# CapPiano.net
KiCad netlist of a schematic drawn in EasyEDA Pro
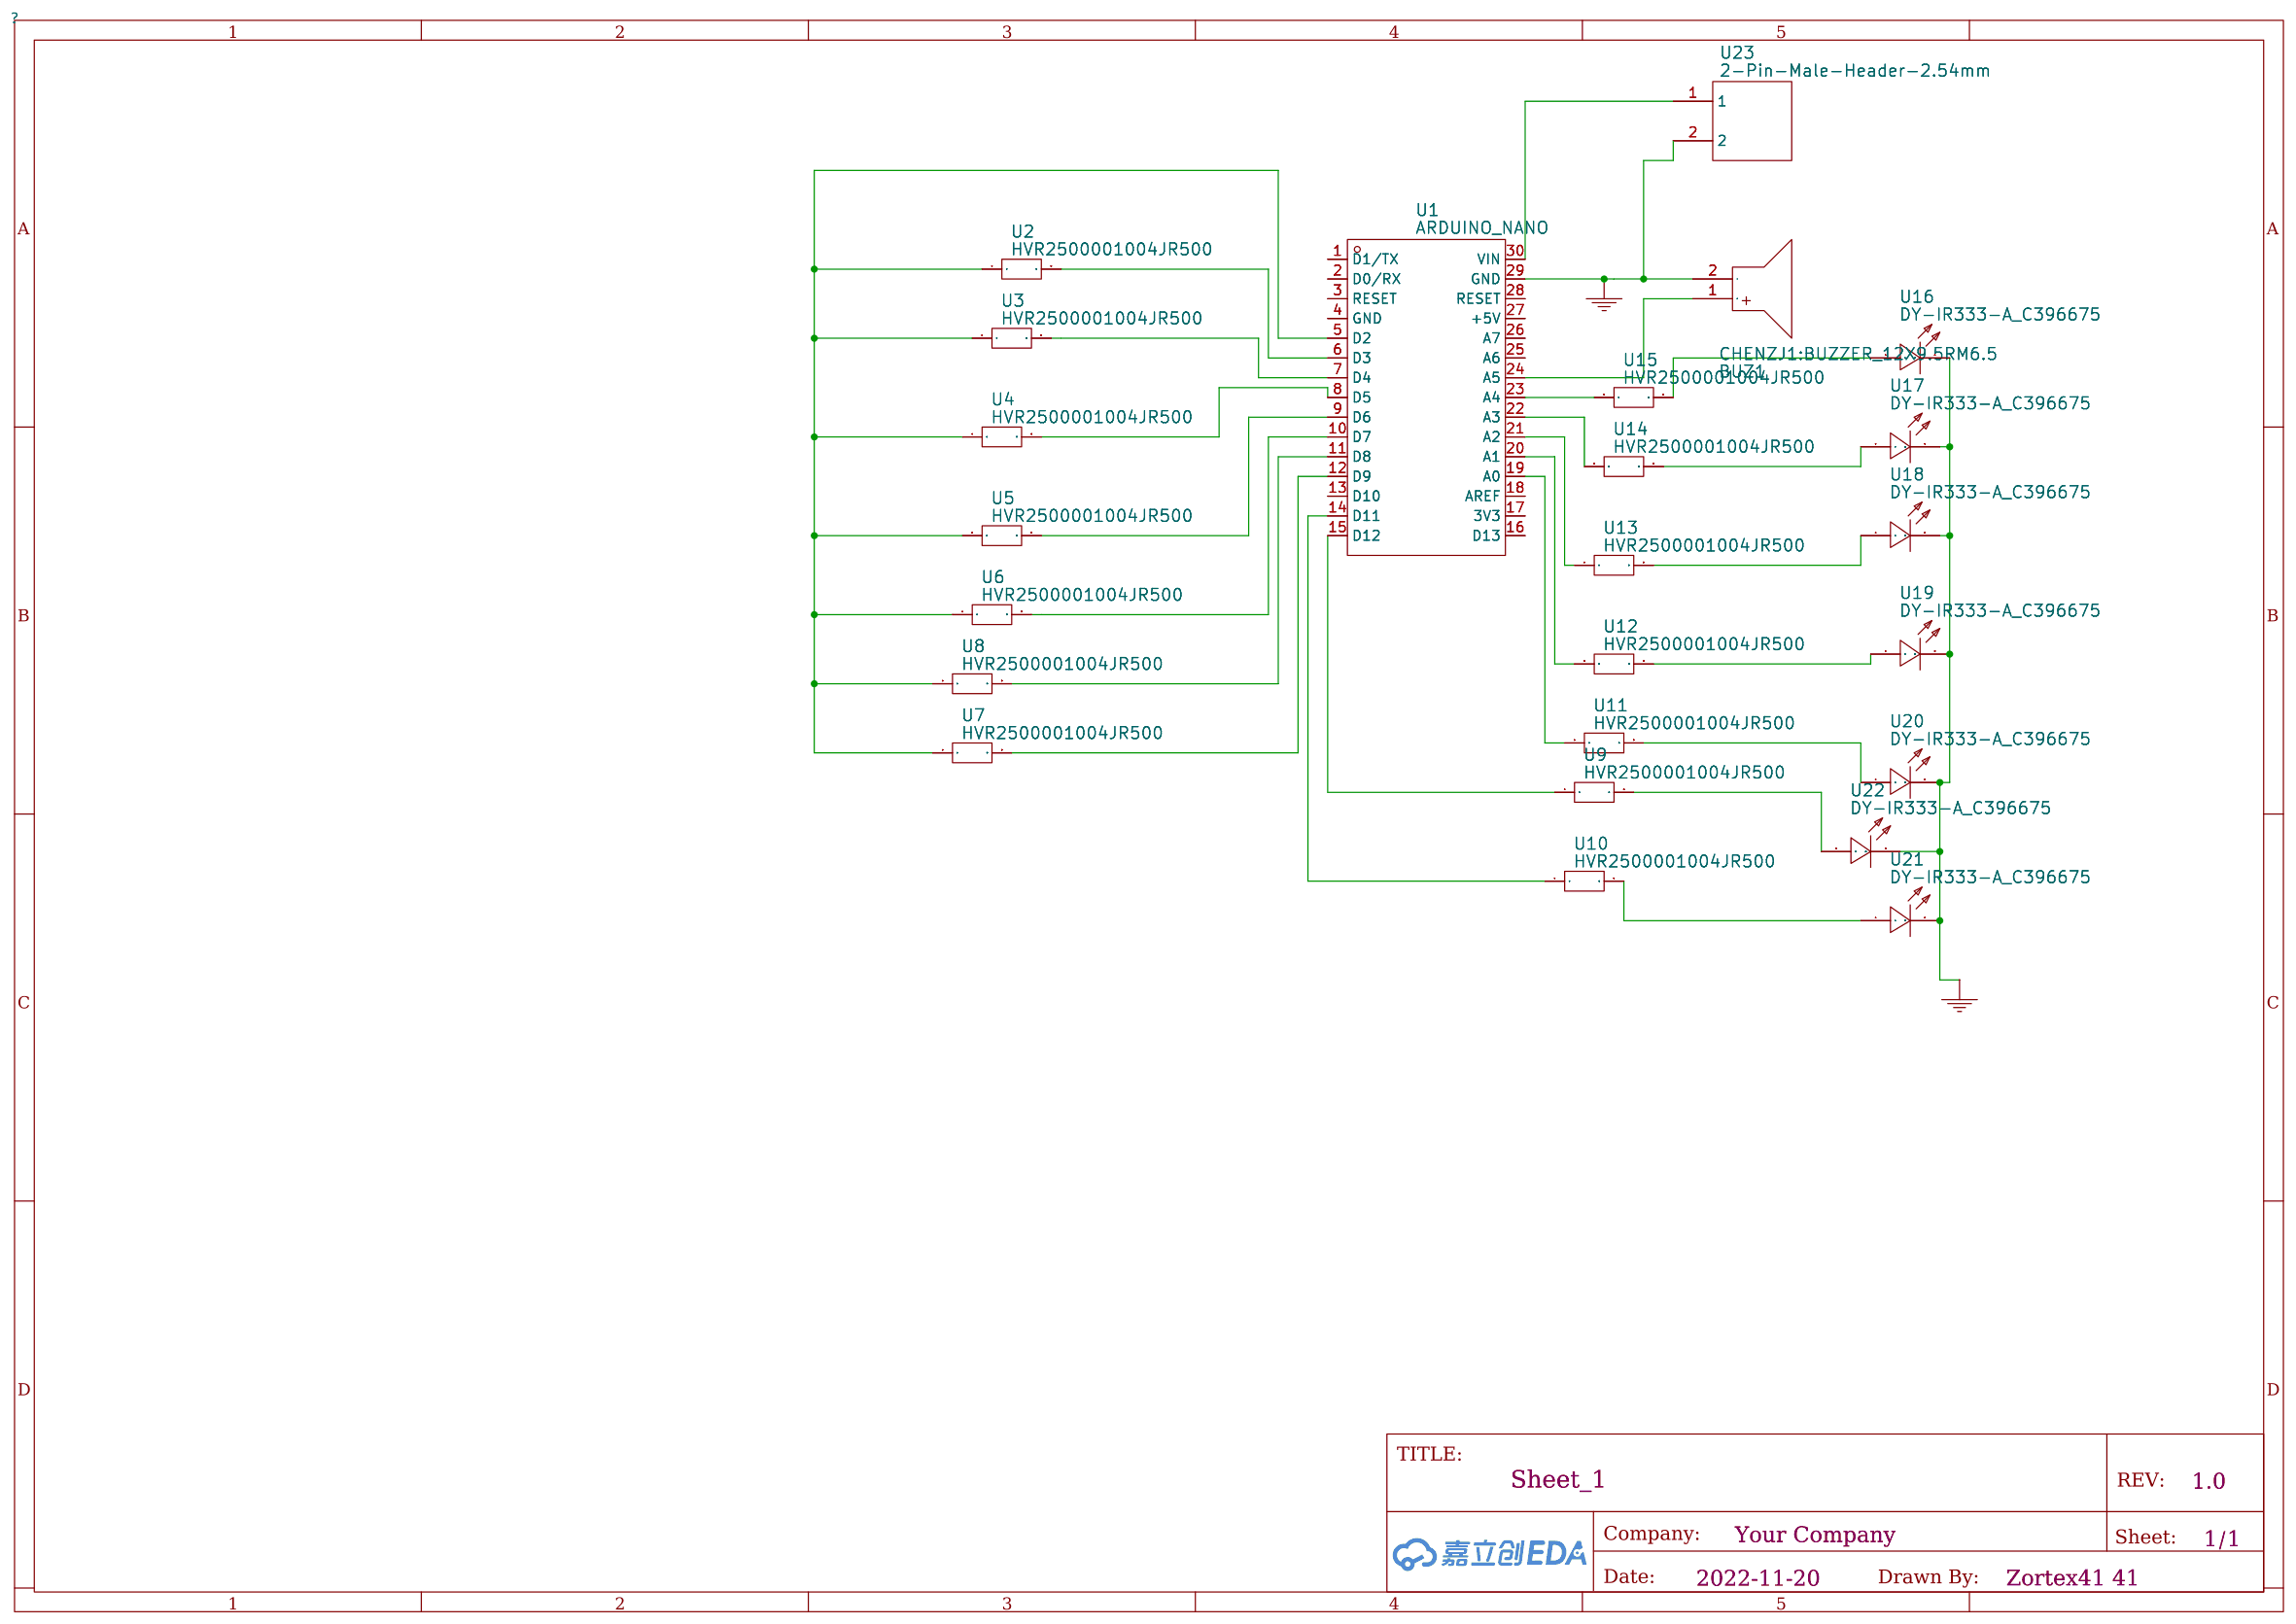
[diagram p0: schematic sheet]

(export (version "E")
  (design (tool "Eeschema 10.0.6"))
  (components
    (comp (ref "BUZ1")
      (value "CHENZJ1:BUZZER_12X9.5RM6.5")
      (footprint "easyedapro:BUZ-TH_BD12.0-P6.50-D0.6_SEA-1285F")
      (fields (field (name "Manufacturer Part") "chenzj1:Buzzer_12x9.5RM6.5"))
      (libsource (lib "easyedapro") (part "CHENZJ1{colon}BUZZER_12X9.5RM6.5"))
    )
    (comp (ref "U1")
      (value "ARDUINO_NANO")
      (footprint "easyedapro:COMM-TH_ARDUINO_NANO")
      (libsource (lib "easyedapro") (part "ARDUINO_NANO"))
    )
    (comp (ref "U2")
      (value "HVR2500001004JR500")
      (footprint "easyedapro:RES-TH_BD2.5-L7.0-P11.00-D0.6")
      (fields (field (name "Manufacturer") "VISHAY(威世)"))
      (libsource (lib "easyedapro") (part "HVR2500001004JR500"))
    )
    (comp (ref "U3")
      (value "HVR2500001004JR500")
      (footprint "easyedapro:RES-TH_BD2.5-L7.0-P11.00-D0.6")
      (fields (field (name "Manufacturer") "VISHAY(威世)"))
      (libsource (lib "easyedapro") (part "HVR2500001004JR500"))
    )
    (comp (ref "U4")
      (value "HVR2500001004JR500")
      (footprint "easyedapro:RES-TH_BD2.5-L7.0-P11.00-D0.6")
      (fields (field (name "Manufacturer") "VISHAY(威世)"))
      (libsource (lib "easyedapro") (part "HVR2500001004JR500"))
    )
    (comp (ref "U5")
      (value "HVR2500001004JR500")
      (footprint "easyedapro:RES-TH_BD2.5-L7.0-P11.00-D0.6")
      (fields (field (name "Manufacturer") "VISHAY(威世)"))
      (libsource (lib "easyedapro") (part "HVR2500001004JR500"))
    )
    (comp (ref "U6")
      (value "HVR2500001004JR500")
      (footprint "easyedapro:RES-TH_BD2.5-L7.0-P11.00-D0.6")
      (fields (field (name "Manufacturer") "VISHAY(威世)"))
      (libsource (lib "easyedapro") (part "HVR2500001004JR500"))
    )
    (comp (ref "U7")
      (value "HVR2500001004JR500")
      (footprint "easyedapro:RES-TH_BD2.5-L7.0-P11.00-D0.6")
      (fields (field (name "Manufacturer") "VISHAY(威世)"))
      (libsource (lib "easyedapro") (part "HVR2500001004JR500"))
    )
    (comp (ref "U8")
      (value "HVR2500001004JR500")
      (footprint "easyedapro:RES-TH_BD2.5-L7.0-P11.00-D0.6")
      (fields (field (name "Manufacturer") "VISHAY(威世)"))
      (libsource (lib "easyedapro") (part "HVR2500001004JR500"))
    )
    (comp (ref "U9")
      (value "HVR2500001004JR500")
      (footprint "easyedapro:RES-TH_BD2.5-L7.0-P11.00-D0.6")
      (fields (field (name "Manufacturer") "VISHAY(威世)"))
      (libsource (lib "easyedapro") (part "HVR2500001004JR500"))
    )
    (comp (ref "U10")
      (value "HVR2500001004JR500")
      (footprint "easyedapro:RES-TH_BD2.5-L7.0-P11.00-D0.6")
      (fields (field (name "Manufacturer") "VISHAY(威世)"))
      (libsource (lib "easyedapro") (part "HVR2500001004JR500"))
    )
    (comp (ref "U11")
      (value "HVR2500001004JR500")
      (footprint "easyedapro:RES-TH_BD2.5-L7.0-P11.00-D0.6")
      (fields (field (name "Manufacturer") "VISHAY(威世)"))
      (libsource (lib "easyedapro") (part "HVR2500001004JR500"))
    )
    (comp (ref "U12")
      (value "HVR2500001004JR500")
      (footprint "easyedapro:RES-TH_BD2.5-L7.0-P11.00-D0.6")
      (fields (field (name "Manufacturer") "VISHAY(威世)"))
      (libsource (lib "easyedapro") (part "HVR2500001004JR500"))
    )
    (comp (ref "U13")
      (value "HVR2500001004JR500")
      (footprint "easyedapro:RES-TH_BD2.5-L7.0-P11.00-D0.6")
      (fields (field (name "Manufacturer") "VISHAY(威世)"))
      (libsource (lib "easyedapro") (part "HVR2500001004JR500"))
    )
    (comp (ref "U14")
      (value "HVR2500001004JR500")
      (footprint "easyedapro:RES-TH_BD2.5-L7.0-P11.00-D0.6")
      (fields (field (name "Manufacturer") "VISHAY(威世)"))
      (libsource (lib "easyedapro") (part "HVR2500001004JR500"))
    )
    (comp (ref "U15")
      (value "HVR2500001004JR500")
      (footprint "easyedapro:RES-TH_BD2.5-L7.0-P11.00-D0.6")
      (fields (field (name "Manufacturer") "VISHAY(威世)"))
      (libsource (lib "easyedapro") (part "HVR2500001004JR500"))
    )
    (comp (ref "U16")
      (value "DY-IR333-A_C396675")
      (footprint "easyedapro:LED-TH_BD5.9-P2.54-FD")
      (fields (field (name "Manufacturer Part") "DY-IR333-A") (field (name "Manufacturer") "TONYU"))
      (libsource (lib "easyedapro") (part "DY-IR333-A_C396675"))
    )
    (comp (ref "U17")
      (value "DY-IR333-A_C396675")
      (footprint "easyedapro:LED-TH_BD5.9-P2.54-FD")
      (fields (field (name "Manufacturer Part") "DY-IR333-A") (field (name "Manufacturer") "TONYU"))
      (libsource (lib "easyedapro") (part "DY-IR333-A_C396675"))
    )
    (comp (ref "U18")
      (value "DY-IR333-A_C396675")
      (footprint "easyedapro:LED-TH_BD5.9-P2.54-FD")
      (fields (field (name "Manufacturer Part") "DY-IR333-A") (field (name "Manufacturer") "TONYU"))
      (libsource (lib "easyedapro") (part "DY-IR333-A_C396675"))
    )
    (comp (ref "U19")
      (value "DY-IR333-A_C396675")
      (footprint "easyedapro:LED-TH_BD5.9-P2.54-FD")
      (fields (field (name "Manufacturer Part") "DY-IR333-A") (field (name "Manufacturer") "TONYU"))
      (libsource (lib "easyedapro") (part "DY-IR333-A_C396675"))
    )
    (comp (ref "U20")
      (value "DY-IR333-A_C396675")
      (footprint "easyedapro:LED-TH_BD5.9-P2.54-FD")
      (fields (field (name "Manufacturer Part") "DY-IR333-A") (field (name "Manufacturer") "TONYU"))
      (libsource (lib "easyedapro") (part "DY-IR333-A_C396675"))
    )
    (comp (ref "U21")
      (value "DY-IR333-A_C396675")
      (footprint "easyedapro:LED-TH_BD5.9-P2.54-FD")
      (fields (field (name "Manufacturer Part") "DY-IR333-A") (field (name "Manufacturer") "TONYU"))
      (libsource (lib "easyedapro") (part "DY-IR333-A_C396675"))
    )
    (comp (ref "U22")
      (value "DY-IR333-A_C396675")
      (footprint "easyedapro:LED-TH_BD5.9-P2.54-FD")
      (fields (field (name "Manufacturer Part") "DY-IR333-A") (field (name "Manufacturer") "TONYU"))
      (libsource (lib "easyedapro") (part "DY-IR333-A_C396675"))
    )
    (comp (ref "U23")
      (value "2-Pin-Male-Header-2.54mm")
      (footprint "easyedapro:2-PIN-MALE-HEADER-2.54MM")
      (libsource (lib "easyedapro") (part "2-Pin-Male-Header-2.54mm"))
    )
  )
  (nets
    (net (code "1") (name "GND") (class "Default")
      (node (ref "BUZ1") (pin "2") (pinfunction "-_2") (pintype "input"))
      (node (ref "U1") (pin "29") (pinfunction "GND_29") (pintype "input"))
      (node (ref "U16") (pin "2") (pinfunction "C_2") (pintype "input"))
      (node (ref "U17") (pin "2") (pinfunction "C_2") (pintype "input"))
      (node (ref "U18") (pin "2") (pinfunction "C_2") (pintype "input"))
      (node (ref "U19") (pin "2") (pinfunction "C_2") (pintype "input"))
      (node (ref "U20") (pin "2") (pinfunction "C_2") (pintype "input"))
      (node (ref "U21") (pin "2") (pinfunction "C_2") (pintype "input"))
      (node (ref "U22") (pin "2") (pinfunction "C_2") (pintype "input"))
      (node (ref "U23") (pin "2") (pinfunction "2_2") (pintype "input"))
    )
    (net (code "2") (name "Net-(BUZ1-+)") (class "Default")
      (node (ref "BUZ1") (pin "1") (pinfunction "+_1") (pintype "input"))
      (node (ref "U1") (pin "24") (pinfunction "A5_24") (pintype "input"))
    )
    (net (code "3") (name "Net-(U1-A0)") (class "Default")
      (node (ref "U1") (pin "19") (pinfunction "A0_19") (pintype "input"))
      (node (ref "U11") (pin "1") (pinfunction "1_1") (pintype "input"))
    )
    (net (code "4") (name "Net-(U1-A1)") (class "Default")
      (node (ref "U1") (pin "20") (pinfunction "A1_20") (pintype "input"))
      (node (ref "U12") (pin "1") (pinfunction "1_1") (pintype "input"))
    )
    (net (code "5") (name "Net-(U1-A2)") (class "Default")
      (node (ref "U1") (pin "21") (pinfunction "A2_21") (pintype "input"))
      (node (ref "U13") (pin "1") (pinfunction "1_1") (pintype "input"))
    )
    (net (code "6") (name "Net-(U1-A3)") (class "Default")
      (node (ref "U1") (pin "22") (pinfunction "A3_22") (pintype "input"))
      (node (ref "U14") (pin "1") (pinfunction "1_1") (pintype "input"))
    )
    (net (code "7") (name "Net-(U1-A4)") (class "Default")
      (node (ref "U1") (pin "23") (pinfunction "A4_23") (pintype "input"))
      (node (ref "U15") (pin "1") (pinfunction "1_1") (pintype "input"))
    )
    (net (code "8") (name "Net-(U1-D2)") (class "Default")
      (node (ref "U1") (pin "5") (pinfunction "D2_5") (pintype "input"))
      (node (ref "U2") (pin "1") (pinfunction "1_1") (pintype "input"))
      (node (ref "U3") (pin "1") (pinfunction "1_1") (pintype "input"))
      (node (ref "U4") (pin "1") (pinfunction "1_1") (pintype "input"))
      (node (ref "U5") (pin "1") (pinfunction "1_1") (pintype "input"))
      (node (ref "U6") (pin "1") (pinfunction "1_1") (pintype "input"))
      (node (ref "U7") (pin "1") (pinfunction "1_1") (pintype "input"))
      (node (ref "U8") (pin "1") (pinfunction "1_1") (pintype "input"))
    )
    (net (code "9") (name "Net-(U1-D3)") (class "Default")
      (node (ref "U1") (pin "6") (pinfunction "D3_6") (pintype "input"))
      (node (ref "U2") (pin "2") (pinfunction "2_2") (pintype "input"))
    )
    (net (code "10") (name "Net-(U1-D4)") (class "Default")
      (node (ref "U1") (pin "7") (pinfunction "D4_7") (pintype "input"))
      (node (ref "U3") (pin "2") (pinfunction "2_2") (pintype "input"))
    )
    (net (code "11") (name "Net-(U1-D5)") (class "Default")
      (node (ref "U1") (pin "8") (pinfunction "D5_8") (pintype "input"))
      (node (ref "U4") (pin "2") (pinfunction "2_2") (pintype "input"))
    )
    (net (code "12") (name "Net-(U1-D6)") (class "Default")
      (node (ref "U1") (pin "9") (pinfunction "D6_9") (pintype "input"))
      (node (ref "U5") (pin "2") (pinfunction "2_2") (pintype "input"))
    )
    (net (code "13") (name "Net-(U1-D7)") (class "Default")
      (node (ref "U1") (pin "10") (pinfunction "D7_10") (pintype "input"))
      (node (ref "U6") (pin "2") (pinfunction "2_2") (pintype "input"))
    )
    (net (code "14") (name "Net-(U1-D8)") (class "Default")
      (node (ref "U1") (pin "11") (pinfunction "D8_11") (pintype "input"))
      (node (ref "U8") (pin "2") (pinfunction "2_2") (pintype "input"))
    )
    (net (code "15") (name "Net-(U1-D9)") (class "Default")
      (node (ref "U1") (pin "12") (pinfunction "D9_12") (pintype "input"))
      (node (ref "U7") (pin "2") (pinfunction "2_2") (pintype "input"))
    )
    (net (code "16") (name "Net-(U1-D11)") (class "Default")
      (node (ref "U1") (pin "14") (pinfunction "D11_14") (pintype "input"))
      (node (ref "U10") (pin "1") (pinfunction "1_1") (pintype "input"))
    )
    (net (code "17") (name "Net-(U1-D12)") (class "Default")
      (node (ref "U1") (pin "15") (pinfunction "D12_15") (pintype "input"))
      (node (ref "U9") (pin "1") (pinfunction "1_1") (pintype "input"))
    )
    (net (code "18") (name "Net-(U1-VIN)") (class "Default")
      (node (ref "U1") (pin "30") (pinfunction "VIN_30") (pintype "input"))
      (node (ref "U23") (pin "1") (pinfunction "1_1") (pintype "input"))
    )
    (net (code "19") (name "Net-(U16-A)") (class "Default")
      (node (ref "U15") (pin "2") (pinfunction "2_2") (pintype "input"))
      (node (ref "U16") (pin "1") (pinfunction "A_1") (pintype "input"))
    )
    (net (code "20") (name "Net-(U17-A)") (class "Default")
      (node (ref "U14") (pin "2") (pinfunction "2_2") (pintype "input"))
      (node (ref "U17") (pin "1") (pinfunction "A_1") (pintype "input"))
    )
    (net (code "21") (name "Net-(U18-A)") (class "Default")
      (node (ref "U13") (pin "2") (pinfunction "2_2") (pintype "input"))
      (node (ref "U18") (pin "1") (pinfunction "A_1") (pintype "input"))
    )
    (net (code "22") (name "Net-(U19-A)") (class "Default")
      (node (ref "U12") (pin "2") (pinfunction "2_2") (pintype "input"))
      (node (ref "U19") (pin "1") (pinfunction "A_1") (pintype "input"))
    )
    (net (code "23") (name "Net-(U20-A)") (class "Default")
      (node (ref "U11") (pin "2") (pinfunction "2_2") (pintype "input"))
      (node (ref "U20") (pin "1") (pinfunction "A_1") (pintype "input"))
    )
    (net (code "24") (name "Net-(U21-A)") (class "Default")
      (node (ref "U10") (pin "2") (pinfunction "2_2") (pintype "input"))
      (node (ref "U21") (pin "1") (pinfunction "A_1") (pintype "input"))
    )
    (net (code "25") (name "Net-(U22-A)") (class "Default")
      (node (ref "U22") (pin "1") (pinfunction "A_1") (pintype "input"))
      (node (ref "U9") (pin "2") (pinfunction "2_2") (pintype "input"))
    )
    (net (code "26") (name "unconnected-(U1-+5V-Pad27)") (class "Default")
      (node (ref "U1") (pin "27") (pinfunction "+5V_27") (pintype "input"))
    )
    (net (code "27") (name "unconnected-(U1-3V3-Pad17)") (class "Default")
      (node (ref "U1") (pin "17") (pinfunction "3V3_17") (pintype "input"))
    )
    (net (code "28") (name "unconnected-(U1-A6-Pad25)") (class "Default")
      (node (ref "U1") (pin "25") (pinfunction "A6_25") (pintype "input"))
    )
    (net (code "29") (name "unconnected-(U1-A7-Pad26)") (class "Default")
      (node (ref "U1") (pin "26") (pinfunction "A7_26") (pintype "input"))
    )
    (net (code "30") (name "unconnected-(U1-AREF-Pad18)") (class "Default")
      (node (ref "U1") (pin "18") (pinfunction "AREF_18") (pintype "input"))
    )
    (net (code "31") (name "unconnected-(U1-D0{slash}RX-Pad2)") (class "Default")
      (node (ref "U1") (pin "2") (pinfunction "D0/RX_2") (pintype "input"))
    )
    (net (code "32") (name "unconnected-(U1-D1{slash}TX-Pad1)") (class "Default")
      (node (ref "U1") (pin "1") (pinfunction "D1/TX_1") (pintype "input"))
    )
    (net (code "33") (name "unconnected-(U1-D10-Pad13)") (class "Default")
      (node (ref "U1") (pin "13") (pinfunction "D10_13") (pintype "input"))
    )
    (net (code "34") (name "unconnected-(U1-D13-Pad16)") (class "Default")
      (node (ref "U1") (pin "16") (pinfunction "D13_16") (pintype "input"))
    )
    (net (code "35") (name "unconnected-(U1-GND-Pad4)") (class "Default")
      (node (ref "U1") (pin "4") (pinfunction "GND_4") (pintype "input"))
    )
    (net (code "36") (name "unconnected-(U1-RESET-Pad3)") (class "Default")
      (node (ref "U1") (pin "3") (pinfunction "RESET_3") (pintype "input"))
    )
    (net (code "37") (name "unconnected-(U1-RESET-Pad28)") (class "Default")
      (node (ref "U1") (pin "28") (pinfunction "RESET_28") (pintype "input"))
    )
  )
)
